# servo_air.net
KiCad netlist of a schematic drawn in EAGLE
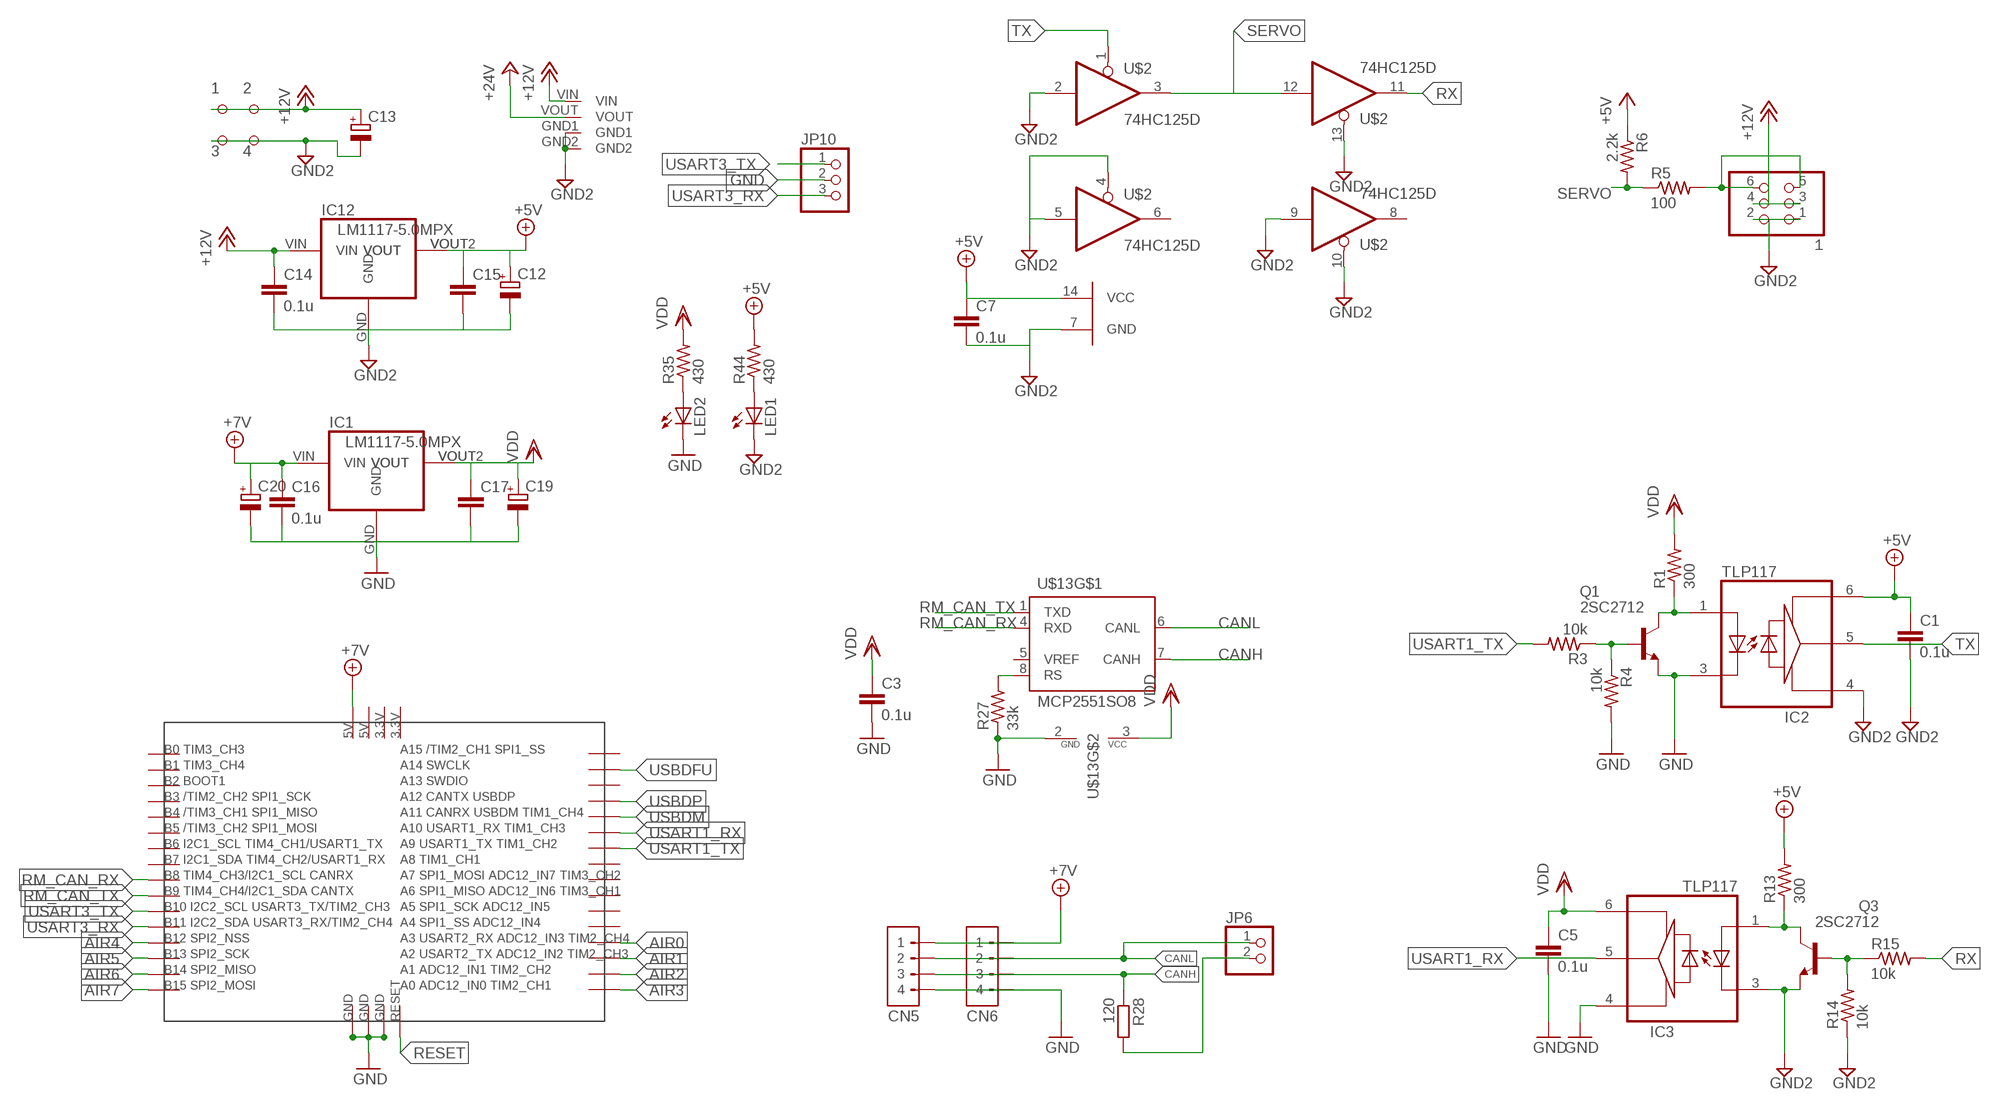
[diagram p0: schematic, sheet 1, part 1 of 2]
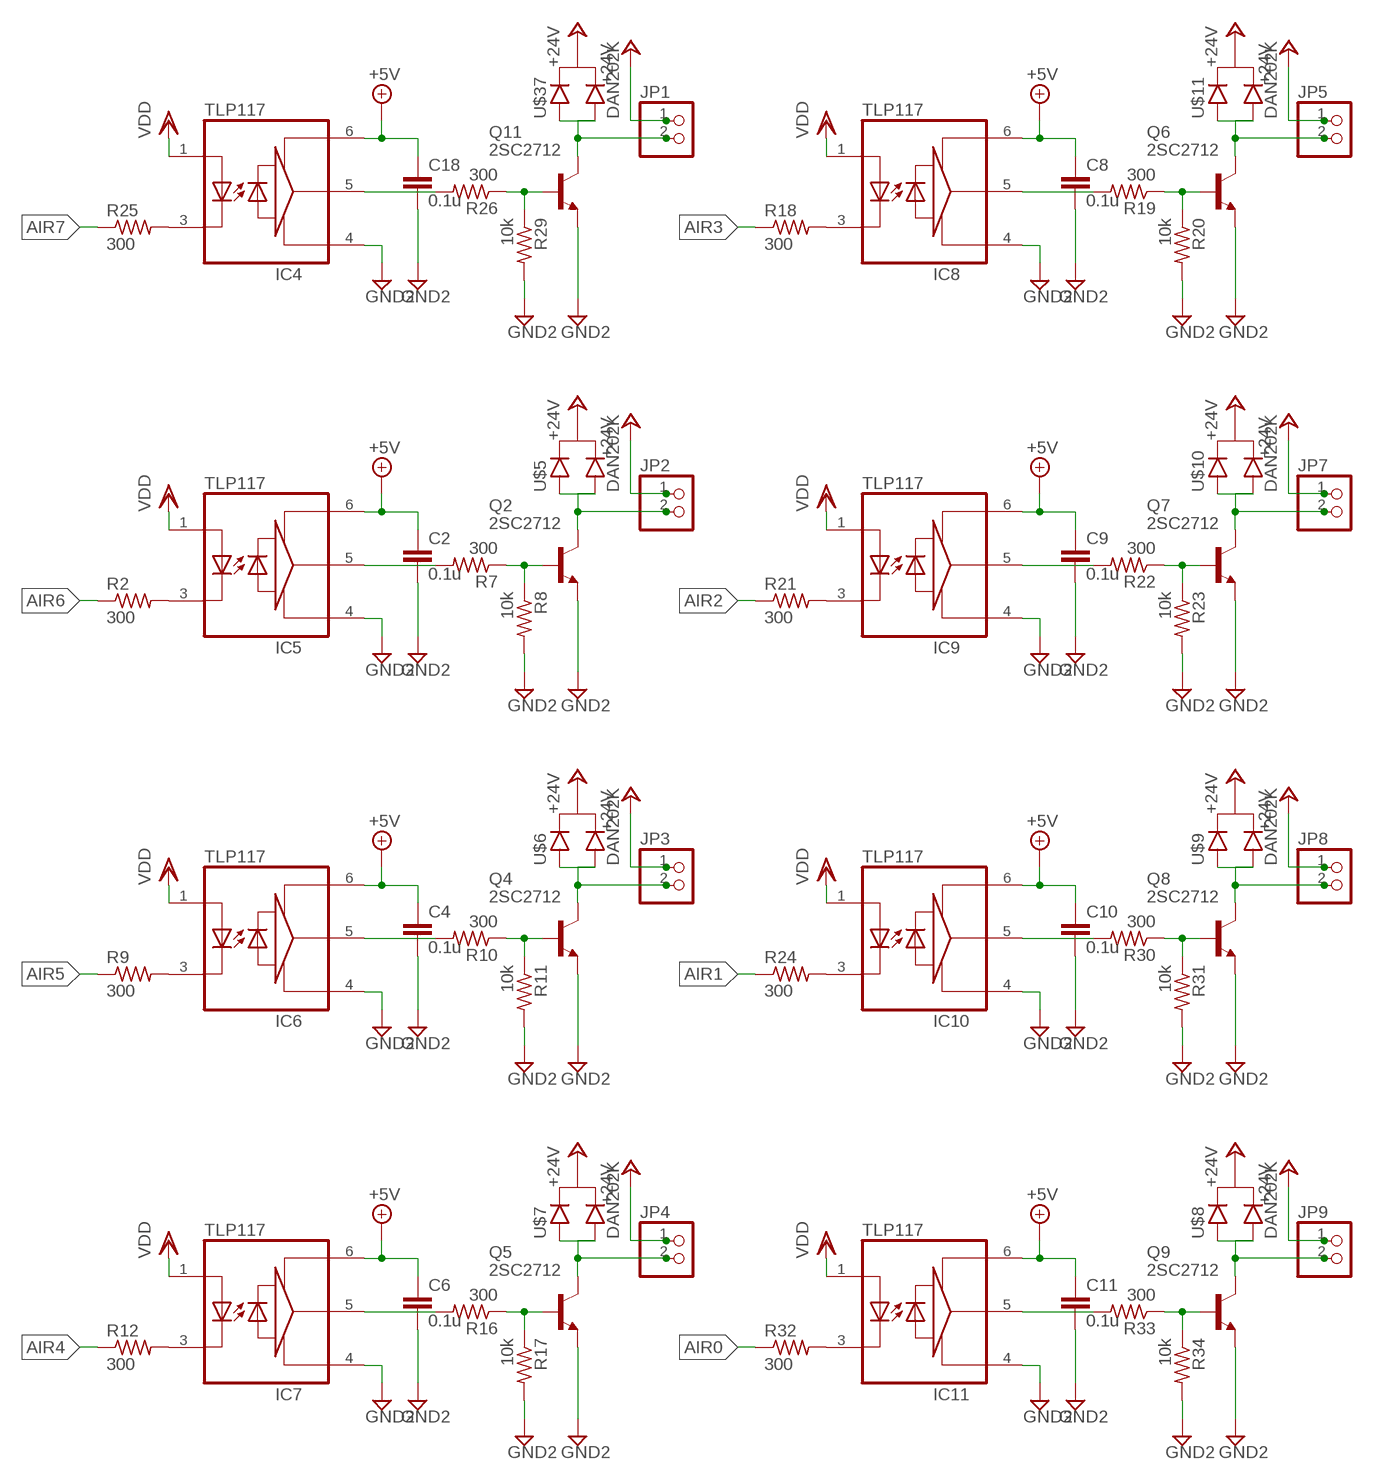
[diagram p1: schematic, sheet 1, part 2 of 2]

(export (version "E")
  (design (tool "Eeschema 10.0.6"))
  (components
    (comp (ref "C1")
      (value "0.1u")
      (footprint "eagle-import:C0603")
      (libsource (lib "eagle-import") (part "C-EUC0603"))
    )
    (comp (ref "C2")
      (value "0.1u")
      (footprint "eagle-import:C2012")
      (libsource (lib "eagle-import") (part "C-EUC2012"))
    )
    (comp (ref "C3")
      (value "0.1u")
      (footprint "eagle-import:C0603")
      (libsource (lib "eagle-import") (part "C-EUC0603"))
    )
    (comp (ref "C4")
      (value "0.1u")
      (footprint "eagle-import:C2012")
      (libsource (lib "eagle-import") (part "C-EUC2012"))
    )
    (comp (ref "C5")
      (value "0.1u")
      (footprint "eagle-import:C0603")
      (libsource (lib "eagle-import") (part "C-EUC0603"))
    )
    (comp (ref "C6")
      (value "0.1u")
      (footprint "eagle-import:C2012")
      (libsource (lib "eagle-import") (part "C-EUC2012"))
    )
    (comp (ref "C7")
      (value "0.1u")
      (footprint "eagle-import:C0603")
      (libsource (lib "eagle-import") (part "C-EUC0603"))
    )
    (comp (ref "C8")
      (value "0.1u")
      (footprint "eagle-import:C2012")
      (libsource (lib "eagle-import") (part "C-EUC2012"))
    )
    (comp (ref "C9")
      (value "0.1u")
      (footprint "eagle-import:C2012")
      (libsource (lib "eagle-import") (part "C-EUC2012"))
    )
    (comp (ref "C10")
      (value "0.1u")
      (footprint "eagle-import:C2012")
      (libsource (lib "eagle-import") (part "C-EUC2012"))
    )
    (comp (ref "C11")
      (value "0.1u")
      (footprint "eagle-import:C2012")
      (libsource (lib "eagle-import") (part "C-EUC2012"))
    )
    (comp (ref "C12")
      (value "CPOL-EUE2.5-6")
      (footprint "eagle-import:E2,5-6")
      (libsource (lib "eagle-import") (part "CPOL-EUE2.5-6"))
    )
    (comp (ref "C13")
      (value "CPOL-EUE2.5-6")
      (footprint "eagle-import:E2,5-6")
      (libsource (lib "eagle-import") (part "CPOL-EUE2.5-6"))
    )
    (comp (ref "C14")
      (value "0.1u")
      (footprint "eagle-import:C0603K")
      (libsource (lib "eagle-import") (part "resistor_C-EUC0603K"))
    )
    (comp (ref "C15")
      (value "C-EUC0603K")
      (footprint "eagle-import:C0603K")
      (libsource (lib "eagle-import") (part "resistor_C-EUC0603K"))
    )
    (comp (ref "C16")
      (value "0.1u")
      (footprint "eagle-import:C0603K")
      (libsource (lib "eagle-import") (part "resistor_C-EUC0603K"))
    )
    (comp (ref "C17")
      (value "C-EUC0603K")
      (footprint "eagle-import:C0603K")
      (libsource (lib "eagle-import") (part "resistor_C-EUC0603K"))
    )
    (comp (ref "C18")
      (value "0.1u")
      (footprint "eagle-import:C2012")
      (libsource (lib "eagle-import") (part "C-EUC2012"))
    )
    (comp (ref "C19")
      (value "CPOL-EUE2.5-6")
      (footprint "eagle-import:E2,5-6")
      (libsource (lib "eagle-import") (part "CPOL-EUE2.5-6"))
    )
    (comp (ref "C20")
      (value "CPOL-EUE2.5-6")
      (footprint "eagle-import:E2,5-6")
      (libsource (lib "eagle-import") (part "CPOL-EUE2.5-6"))
    )
    (comp (ref "CN5")
      (value "CN4-JST-XH-TOP")
      (footprint "eagle-import:JST-B4B-XH-A")
      (libsource (lib "eagle-import") (part "CN4-JST-XH-TOP"))
    )
    (comp (ref "CN6")
      (value "CN4-JST-XH-TOP")
      (footprint "eagle-import:JST-B4B-XH-A")
      (libsource (lib "eagle-import") (part "CN4-JST-XH-TOP"))
    )
    (comp (ref "IC1")
      (value "LM1117-5.0MPX")
      (footprint "eagle-import:SOT223")
      (libsource (lib "eagle-import") (part "LM1117IMP-5.0"))
    )
    (comp (ref "IC2")
      (value "TLP117")
      (footprint "eagle-import:MFSOP6")
      (libsource (lib "eagle-import") (part "TLP117"))
    )
    (comp (ref "IC3")
      (value "TLP117")
      (footprint "eagle-import:MFSOP6")
      (libsource (lib "eagle-import") (part "TLP117"))
    )
    (comp (ref "IC4")
      (value "TLP117")
      (footprint "eagle-import:MFSOP6")
      (libsource (lib "eagle-import") (part "TLP117"))
    )
    (comp (ref "IC5")
      (value "TLP117")
      (footprint "eagle-import:MFSOP6")
      (libsource (lib "eagle-import") (part "TLP117"))
    )
    (comp (ref "IC6")
      (value "TLP117")
      (footprint "eagle-import:MFSOP6")
      (libsource (lib "eagle-import") (part "TLP117"))
    )
    (comp (ref "IC7")
      (value "TLP117")
      (footprint "eagle-import:MFSOP6")
      (libsource (lib "eagle-import") (part "TLP117"))
    )
    (comp (ref "IC8")
      (value "TLP117")
      (footprint "eagle-import:MFSOP6")
      (libsource (lib "eagle-import") (part "TLP117"))
    )
    (comp (ref "IC9")
      (value "TLP117")
      (footprint "eagle-import:MFSOP6")
      (libsource (lib "eagle-import") (part "TLP117"))
    )
    (comp (ref "IC10")
      (value "TLP117")
      (footprint "eagle-import:MFSOP6")
      (libsource (lib "eagle-import") (part "TLP117"))
    )
    (comp (ref "IC11")
      (value "TLP117")
      (footprint "eagle-import:MFSOP6")
      (libsource (lib "eagle-import") (part "TLP117"))
    )
    (comp (ref "IC12")
      (value "LM1117-5.0MPX")
      (footprint "eagle-import:SOT223")
      (libsource (lib "eagle-import") (part "LM1117IMP-5.0"))
    )
    (comp (ref "JP1")
      (value "PINHD-1X2/90")
      (footprint "eagle-import:1X02_90")
      (libsource (lib "eagle-import") (part "PINHD-1X2/90"))
    )
    (comp (ref "JP2")
      (value "PINHD-1X2/90")
      (footprint "eagle-import:1X02_90")
      (libsource (lib "eagle-import") (part "PINHD-1X2/90"))
    )
    (comp (ref "JP3")
      (value "PINHD-1X2/90")
      (footprint "eagle-import:1X02_90")
      (libsource (lib "eagle-import") (part "PINHD-1X2/90"))
    )
    (comp (ref "JP4")
      (value "PINHD-1X2/90")
      (footprint "eagle-import:1X02_90")
      (libsource (lib "eagle-import") (part "PINHD-1X2/90"))
    )
    (comp (ref "JP5")
      (value "PINHD-1X2/90")
      (footprint "eagle-import:1X02_90")
      (libsource (lib "eagle-import") (part "PINHD-1X2/90"))
    )
    (comp (ref "JP6")
      (value "PINHD-1X2")
      (footprint "eagle-import:1X02")
      (libsource (lib "eagle-import") (part "PINHD-1X2"))
    )
    (comp (ref "JP7")
      (value "PINHD-1X2/90")
      (footprint "eagle-import:1X02_90")
      (libsource (lib "eagle-import") (part "PINHD-1X2/90"))
    )
    (comp (ref "JP8")
      (value "PINHD-1X2/90")
      (footprint "eagle-import:1X02_90")
      (libsource (lib "eagle-import") (part "PINHD-1X2/90"))
    )
    (comp (ref "JP9")
      (value "PINHD-1X2/90")
      (footprint "eagle-import:1X02_90")
      (libsource (lib "eagle-import") (part "PINHD-1X2/90"))
    )
    (comp (ref "JP10")
      (value "PINHD-1X3")
      (footprint "eagle-import:1X03")
      (libsource (lib "eagle-import") (part "PINHD-1X3"))
    )
    (comp (ref "LED1")
      (value "LEDCHIPLED_1206")
      (footprint "eagle-import:CHIPLED_1206")
      (libsource (lib "eagle-import") (part "LEDCHIPLED_1206"))
    )
    (comp (ref "LED2")
      (value "LEDCHIPLED_1206")
      (footprint "eagle-import:CHIPLED_1206")
      (libsource (lib "eagle-import") (part "LEDCHIPLED_1206"))
    )
    (comp (ref "Q1")
      (value "2SC2712")
      (footprint "eagle-import:SC-59(TYPE1)")
      (libsource (lib "eagle-import") (part "2SC2712"))
    )
    (comp (ref "Q2")
      (value "2SC2712")
      (footprint "eagle-import:SC-59(TYPE1)")
      (libsource (lib "eagle-import") (part "2SC2712"))
    )
    (comp (ref "Q3")
      (value "2SC2712")
      (footprint "eagle-import:SC-59(TYPE1)")
      (libsource (lib "eagle-import") (part "2SC2712"))
    )
    (comp (ref "Q4")
      (value "2SC2712")
      (footprint "eagle-import:SC-59(TYPE1)")
      (libsource (lib "eagle-import") (part "2SC2712"))
    )
    (comp (ref "Q5")
      (value "2SC2712")
      (footprint "eagle-import:SC-59(TYPE1)")
      (libsource (lib "eagle-import") (part "2SC2712"))
    )
    (comp (ref "Q6")
      (value "2SC2712")
      (footprint "eagle-import:SC-59(TYPE1)")
      (libsource (lib "eagle-import") (part "2SC2712"))
    )
    (comp (ref "Q7")
      (value "2SC2712")
      (footprint "eagle-import:SC-59(TYPE1)")
      (libsource (lib "eagle-import") (part "2SC2712"))
    )
    (comp (ref "Q8")
      (value "2SC2712")
      (footprint "eagle-import:SC-59(TYPE1)")
      (libsource (lib "eagle-import") (part "2SC2712"))
    )
    (comp (ref "Q9")
      (value "2SC2712")
      (footprint "eagle-import:SC-59(TYPE1)")
      (libsource (lib "eagle-import") (part "2SC2712"))
    )
    (comp (ref "Q11")
      (value "2SC2712")
      (footprint "eagle-import:SC-59(TYPE1)")
      (libsource (lib "eagle-import") (part "2SC2712"))
    )
    (comp (ref "R1")
      (value "300")
      (footprint "eagle-import:R0603")
      (libsource (lib "eagle-import") (part "R-US_R0603"))
    )
    (comp (ref "R2")
      (value "300")
      (footprint "eagle-import:R2012")
      (libsource (lib "eagle-import") (part "R-US_R2012"))
    )
    (comp (ref "R3")
      (value "10k")
      (footprint "eagle-import:R0603")
      (libsource (lib "eagle-import") (part "R-US_R0603"))
    )
    (comp (ref "R4")
      (value "10k")
      (footprint "eagle-import:R0603")
      (libsource (lib "eagle-import") (part "R-US_R0603"))
    )
    (comp (ref "R5")
      (value "100")
      (footprint "eagle-import:R0603")
      (libsource (lib "eagle-import") (part "R-US_R0603"))
    )
    (comp (ref "R6")
      (value "2.2k")
      (footprint "eagle-import:R0603")
      (libsource (lib "eagle-import") (part "R-US_R0603"))
    )
    (comp (ref "R7")
      (value "300")
      (footprint "eagle-import:R2012")
      (libsource (lib "eagle-import") (part "R-US_R2012"))
    )
    (comp (ref "R8")
      (value "10k")
      (footprint "eagle-import:R2012")
      (libsource (lib "eagle-import") (part "R-US_R2012"))
    )
    (comp (ref "R9")
      (value "300")
      (footprint "eagle-import:R2012")
      (libsource (lib "eagle-import") (part "R-US_R2012"))
    )
    (comp (ref "R10")
      (value "300")
      (footprint "eagle-import:R2012")
      (libsource (lib "eagle-import") (part "R-US_R2012"))
    )
    (comp (ref "R11")
      (value "10k")
      (footprint "eagle-import:R2012")
      (libsource (lib "eagle-import") (part "R-US_R2012"))
    )
    (comp (ref "R12")
      (value "300")
      (footprint "eagle-import:R2012")
      (libsource (lib "eagle-import") (part "R-US_R2012"))
    )
    (comp (ref "R13")
      (value "300")
      (footprint "eagle-import:R0603")
      (libsource (lib "eagle-import") (part "R-US_R0603"))
    )
    (comp (ref "R14")
      (value "10k")
      (footprint "eagle-import:R0603")
      (libsource (lib "eagle-import") (part "R-US_R0603"))
    )
    (comp (ref "R15")
      (value "10k")
      (footprint "eagle-import:R0603")
      (libsource (lib "eagle-import") (part "R-US_R0603"))
    )
    (comp (ref "R16")
      (value "300")
      (footprint "eagle-import:R2012")
      (libsource (lib "eagle-import") (part "R-US_R2012"))
    )
    (comp (ref "R17")
      (value "10k")
      (footprint "eagle-import:R2012")
      (libsource (lib "eagle-import") (part "R-US_R2012"))
    )
    (comp (ref "R18")
      (value "300")
      (footprint "eagle-import:R2012")
      (libsource (lib "eagle-import") (part "R-US_R2012"))
    )
    (comp (ref "R19")
      (value "300")
      (footprint "eagle-import:R2012")
      (libsource (lib "eagle-import") (part "R-US_R2012"))
    )
    (comp (ref "R20")
      (value "10k")
      (footprint "eagle-import:R2012")
      (libsource (lib "eagle-import") (part "R-US_R2012"))
    )
    (comp (ref "R21")
      (value "300")
      (footprint "eagle-import:R2012")
      (libsource (lib "eagle-import") (part "R-US_R2012"))
    )
    (comp (ref "R22")
      (value "300")
      (footprint "eagle-import:R2012")
      (libsource (lib "eagle-import") (part "R-US_R2012"))
    )
    (comp (ref "R23")
      (value "10k")
      (footprint "eagle-import:R2012")
      (libsource (lib "eagle-import") (part "R-US_R2012"))
    )
    (comp (ref "R24")
      (value "300")
      (footprint "eagle-import:R2012")
      (libsource (lib "eagle-import") (part "R-US_R2012"))
    )
    (comp (ref "R25")
      (value "300")
      (footprint "eagle-import:R2012")
      (libsource (lib "eagle-import") (part "R-US_R2012"))
    )
    (comp (ref "R26")
      (value "300")
      (footprint "eagle-import:R2012")
      (libsource (lib "eagle-import") (part "R-US_R2012"))
    )
    (comp (ref "R27")
      (value "33k")
      (footprint "eagle-import:R0603")
      (libsource (lib "eagle-import") (part "resistor_R-US_R0603"))
    )
    (comp (ref "R28")
      (value "120")
      (footprint "eagle-import:R0603")
      (libsource (lib "eagle-import") (part "R-EU_R0603"))
    )
    (comp (ref "R29")
      (value "10k")
      (footprint "eagle-import:R2012")
      (libsource (lib "eagle-import") (part "R-US_R2012"))
    )
    (comp (ref "R30")
      (value "300")
      (footprint "eagle-import:R2012")
      (libsource (lib "eagle-import") (part "R-US_R2012"))
    )
    (comp (ref "R31")
      (value "10k")
      (footprint "eagle-import:R2012")
      (libsource (lib "eagle-import") (part "R-US_R2012"))
    )
    (comp (ref "R32")
      (value "300")
      (footprint "eagle-import:R2012")
      (libsource (lib "eagle-import") (part "R-US_R2012"))
    )
    (comp (ref "R33")
      (value "300")
      (footprint "eagle-import:R2012")
      (libsource (lib "eagle-import") (part "R-US_R2012"))
    )
    (comp (ref "R34")
      (value "10k")
      (footprint "eagle-import:R2012")
      (libsource (lib "eagle-import") (part "R-US_R2012"))
    )
    (comp (ref "R35")
      (value "430")
      (footprint "eagle-import:M2012")
      (libsource (lib "eagle-import") (part "R-US_M2012"))
    )
    (comp (ref "R44")
      (value "430")
      (footprint "eagle-import:M2012")
      (libsource (lib "eagle-import") (part "R-US_M2012"))
    )
    (comp (ref "U$1")
      (value "STBE_MINI")
      (footprint "eagle-import:STBEE_MINI")
      (libsource (lib "eagle-import") (part "STBE_MINI"))
    )
    (comp (ref "U$2")
      (value "74HC125D")
      (footprint "eagle-import:SO14")
      (libsource (lib "eagle-import") (part "74HC125D"))
    )
    (comp (ref "U$3")
      (value "5569")
      (footprint "eagle-import:5569")
      (libsource (lib "eagle-import") (part "5569"))
    )
    (comp (ref "U$4")
      (value "LT3580")
      (footprint "eagle-import:LT3580")
      (libsource (lib "eagle-import") (part "LT3580"))
    )
    (comp (ref "U$5")
      (value "DAN202K")
      (footprint "eagle-import:SC-59")
      (libsource (lib "eagle-import") (part "DAN202K"))
    )
    (comp (ref "U$6")
      (value "DAN202K")
      (footprint "eagle-import:SC-59")
      (libsource (lib "eagle-import") (part "DAN202K"))
    )
    (comp (ref "U$7")
      (value "DAN202K")
      (footprint "eagle-import:SC-59")
      (libsource (lib "eagle-import") (part "DAN202K"))
    )
    (comp (ref "U$8")
      (value "DAN202K")
      (footprint "eagle-import:SC-59")
      (libsource (lib "eagle-import") (part "DAN202K"))
    )
    (comp (ref "U$9")
      (value "DAN202K")
      (footprint "eagle-import:SC-59")
      (libsource (lib "eagle-import") (part "DAN202K"))
    )
    (comp (ref "U$10")
      (value "DAN202K")
      (footprint "eagle-import:SC-59")
      (libsource (lib "eagle-import") (part "DAN202K"))
    )
    (comp (ref "U$11")
      (value "DAN202K")
      (footprint "eagle-import:SC-59")
      (libsource (lib "eagle-import") (part "DAN202K"))
    )
    (comp (ref "U$13")
      (value "MCP2551SO8")
      (footprint "eagle-import:SO08")
      (libsource (lib "eagle-import") (part "MCP2551SO8"))
    )
    (comp (ref "U$37")
      (value "DAN202K")
      (footprint "eagle-import:SC-59")
      (libsource (lib "eagle-import") (part "DAN202K"))
    )
    (comp (ref "　　1")
      (value "PINHD-2X3/90")
      (footprint "eagle-import:2X03_90")
      (libsource (lib "eagle-import") (part "PINHD-2X3/90"))
    )
  )
  (nets
    (net (code "1") (name "+5V") (class "Default")
      (node (ref "C1") (pin "1") (pinfunction "1_1") (pintype "passive"))
      (node (ref "C10") (pin "1") (pinfunction "1_1") (pintype "passive"))
      (node (ref "C11") (pin "1") (pinfunction "1_1") (pintype "passive"))
      (node (ref "C12") (pin "+") (pinfunction "+_+") (pintype "passive"))
      (node (ref "C15") (pin "1") (pinfunction "1_1") (pintype "passive"))
      (node (ref "C18") (pin "1") (pinfunction "1_1") (pintype "passive"))
      (node (ref "C2") (pin "1") (pinfunction "1_1") (pintype "passive"))
      (node (ref "C4") (pin "1") (pinfunction "1_1") (pintype "passive"))
      (node (ref "C6") (pin "1") (pinfunction "1_1") (pintype "passive"))
      (node (ref "C7") (pin "1") (pinfunction "1_1") (pintype "passive"))
      (node (ref "C8") (pin "1") (pinfunction "1_1") (pintype "passive"))
      (node (ref "C9") (pin "1") (pinfunction "1_1") (pintype "passive"))
      (node (ref "IC10") (pin "6") (pinfunction "VCC_6") (pintype "power_in"))
      (node (ref "IC11") (pin "6") (pinfunction "VCC_6") (pintype "power_in"))
      (node (ref "IC12") (pin "VOUT") (pinfunction "VOUT_VOUT") (pintype "output"))
      (node (ref "IC12") (pin "VOUT2") (pinfunction "VOUT_VOUT2") (pintype "output"))
      (node (ref "IC2") (pin "6") (pinfunction "VCC_6") (pintype "power_in"))
      (node (ref "IC4") (pin "6") (pinfunction "VCC_6") (pintype "power_in"))
      (node (ref "IC5") (pin "6") (pinfunction "VCC_6") (pintype "power_in"))
      (node (ref "IC6") (pin "6") (pinfunction "VCC_6") (pintype "power_in"))
      (node (ref "IC7") (pin "6") (pinfunction "VCC_6") (pintype "power_in"))
      (node (ref "IC8") (pin "6") (pinfunction "VCC_6") (pintype "power_in"))
      (node (ref "IC9") (pin "6") (pinfunction "VCC_6") (pintype "power_in"))
      (node (ref "R13") (pin "2") (pinfunction "2_2") (pintype "passive"))
      (node (ref "R44") (pin "2") (pinfunction "2_2") (pintype "passive"))
      (node (ref "R6") (pin "1") (pinfunction "1_1") (pintype "passive"))
      (node (ref "U$2") (pin "14") (pinfunction "VCC_14") (pintype "bidirectional"))
    )
    (net (code "2") (name "+7V") (class "Default")
      (node (ref "C16") (pin "1") (pinfunction "1_1") (pintype "passive"))
      (node (ref "C20") (pin "+") (pinfunction "+_+") (pintype "passive"))
      (node (ref "CN5") (pin "1") (pinfunction "1_1") (pintype "passive"))
      (node (ref "CN6") (pin "1") (pinfunction "1_1") (pintype "passive"))
      (node (ref "IC1") (pin "VIN") (pinfunction "VIN_VIN") (pintype "input"))
      (node (ref "U$1") (pin "5V1") (pinfunction "5V1_5V1") (pintype "bidirectional"))
    )
    (net (code "3") (name "+12V") (class "Default")
      (node (ref "C13") (pin "+") (pinfunction "+_+") (pintype "passive"))
      (node (ref "C14") (pin "1") (pinfunction "1_1") (pintype "passive"))
      (node (ref "IC12") (pin "VIN") (pinfunction "VIN_VIN") (pintype "input"))
      (node (ref "U$3") (pin "1") (pinfunction "1_1") (pintype "bidirectional"))
      (node (ref "U$3") (pin "2") (pinfunction "2_2") (pintype "bidirectional"))
      (node (ref "U$4") (pin "VIN") (pinfunction "VIN_VIN") (pintype "bidirectional"))
      (node (ref "　　1") (pin "3") (pinfunction "3_3") (pintype "passive"))
      (node (ref "　　1") (pin "4") (pinfunction "4_4") (pintype "passive"))
    )
    (net (code "4") (name "+24V") (class "Default")
      (node (ref "JP1") (pin "1") (pinfunction "1_1") (pintype "passive"))
      (node (ref "JP2") (pin "1") (pinfunction "1_1") (pintype "passive"))
      (node (ref "JP3") (pin "1") (pinfunction "1_1") (pintype "passive"))
      (node (ref "JP4") (pin "1") (pinfunction "1_1") (pintype "passive"))
      (node (ref "JP5") (pin "1") (pinfunction "1_1") (pintype "passive"))
      (node (ref "JP7") (pin "1") (pinfunction "1_1") (pintype "passive"))
      (node (ref "JP8") (pin "1") (pinfunction "1_1") (pintype "passive"))
      (node (ref "JP9") (pin "1") (pinfunction "1_1") (pintype "passive"))
      (node (ref "U$10") (pin "K") (pinfunction "K_K") (pintype "passive"))
      (node (ref "U$11") (pin "K") (pinfunction "K_K") (pintype "passive"))
      (node (ref "U$37") (pin "K") (pinfunction "K_K") (pintype "passive"))
      (node (ref "U$4") (pin "VOUT") (pinfunction "VOUT_VOUT") (pintype "bidirectional"))
      (node (ref "U$5") (pin "K") (pinfunction "K_K") (pintype "passive"))
      (node (ref "U$6") (pin "K") (pinfunction "K_K") (pintype "passive"))
      (node (ref "U$7") (pin "K") (pinfunction "K_K") (pintype "passive"))
      (node (ref "U$8") (pin "K") (pinfunction "K_K") (pintype "passive"))
      (node (ref "U$9") (pin "K") (pinfunction "K_K") (pintype "passive"))
    )
    (net (code "5") (name "AIR0") (class "Default")
      (node (ref "R32") (pin "1") (pinfunction "1_1") (pintype "passive"))
      (node (ref "U$1") (pin "A3") (pinfunction "A3_A3") (pintype "bidirectional"))
    )
    (net (code "6") (name "AIR1") (class "Default")
      (node (ref "R24") (pin "1") (pinfunction "1_1") (pintype "passive"))
      (node (ref "U$1") (pin "A2") (pinfunction "A2_A2") (pintype "bidirectional"))
    )
    (net (code "7") (name "AIR2") (class "Default")
      (node (ref "R21") (pin "1") (pinfunction "1_1") (pintype "passive"))
      (node (ref "U$1") (pin "A1") (pinfunction "A1_A1") (pintype "bidirectional"))
    )
    (net (code "8") (name "AIR3") (class "Default")
      (node (ref "R18") (pin "1") (pinfunction "1_1") (pintype "passive"))
      (node (ref "U$1") (pin "A0") (pinfunction "A0_A0") (pintype "bidirectional"))
    )
    (net (code "9") (name "AIR4") (class "Default")
      (node (ref "R12") (pin "1") (pinfunction "1_1") (pintype "passive"))
      (node (ref "U$1") (pin "B12") (pinfunction "B12_B12") (pintype "bidirectional"))
    )
    (net (code "10") (name "AIR5") (class "Default")
      (node (ref "R9") (pin "1") (pinfunction "1_1") (pintype "passive"))
      (node (ref "U$1") (pin "B13") (pinfunction "B13_B13") (pintype "bidirectional"))
    )
    (net (code "11") (name "AIR6") (class "Default")
      (node (ref "R2") (pin "1") (pinfunction "1_1") (pintype "passive"))
      (node (ref "U$1") (pin "B14") (pinfunction "B14_B14") (pintype "bidirectional"))
    )
    (net (code "12") (name "AIR7") (class "Default")
      (node (ref "R25") (pin "1") (pinfunction "1_1") (pintype "passive"))
      (node (ref "U$1") (pin "B15") (pinfunction "B15_B15") (pintype "bidirectional"))
    )
    (net (code "13") (name "CANH") (class "Default")
      (node (ref "CN5") (pin "3") (pinfunction "3_3") (pintype "passive"))
      (node (ref "CN6") (pin "3") (pinfunction "3_3") (pintype "passive"))
      (node (ref "R28") (pin "1") (pinfunction "1_1") (pintype "passive"))
      (node (ref "U$13") (pin "7") (pinfunction "CANH_7") (pintype "bidirectional"))
    )
    (net (code "14") (name "CANL") (class "Default")
      (node (ref "CN5") (pin "2") (pinfunction "2_2") (pintype "passive"))
      (node (ref "CN6") (pin "2") (pinfunction "2_2") (pintype "passive"))
      (node (ref "JP6") (pin "1") (pinfunction "1_1") (pintype "passive"))
      (node (ref "U$13") (pin "6") (pinfunction "CANL_6") (pintype "bidirectional"))
    )
    (net (code "15") (name "GND") (class "Default")
      (node (ref "C16") (pin "2") (pinfunction "2_2") (pintype "passive"))
      (node (ref "C17") (pin "2") (pinfunction "2_2") (pintype "passive"))
      (node (ref "C19") (pin "-") (pinfunction "-_-") (pintype "passive"))
      (node (ref "C20") (pin "-") (pinfunction "-_-") (pintype "passive"))
      (node (ref "C3") (pin "2") (pinfunction "2_2") (pintype "passive"))
      (node (ref "C5") (pin "2") (pinfunction "2_2") (pintype "passive"))
      (node (ref "CN5") (pin "4") (pinfunction "4_4") (pintype "passive"))
      (node (ref "CN6") (pin "4") (pinfunction "4_4") (pintype "passive"))
      (node (ref "IC1") (pin "GND") (pinfunction "GND_GND") (pintype "power_in"))
      (node (ref "IC2") (pin "3") (pinfunction "3_3") (pintype "output"))
      (node (ref "IC3") (pin "4") (pinfunction "GND_4") (pintype "power_in"))
      (node (ref "JP10") (pin "2") (pinfunction "2_2") (pintype "passive"))
      (node (ref "LED2") (pin "C") (pinfunction "C_C") (pintype "passive"))
      (node (ref "Q1") (pin "E") (pinfunction "E_E") (pintype "passive"))
      (node (ref "R27") (pin "1") (pinfunction "1_1") (pintype "passive"))
      (node (ref "R4") (pin "2") (pinfunction "2_2") (pintype "passive"))
      (node (ref "U$1") (pin "GND1") (pinfunction "GND1_GND1") (pintype "bidirectional"))
      (node (ref "U$1") (pin "GND2") (pinfunction "GND2_GND2") (pintype "bidirectional"))
      (node (ref "U$1") (pin "GND3") (pinfunction "GND3_GND3") (pintype "bidirectional"))
      (node (ref "U$13") (pin "2") (pinfunction "GND_2") (pintype "power_in"))
    )
    (net (code "16") (name "GND2") (class "Default")
      (node (ref "C1") (pin "2") (pinfunction "2_2") (pintype "passive"))
      (node (ref "C10") (pin "2") (pinfunction "2_2") (pintype "passive"))
      (node (ref "C11") (pin "2") (pinfunction "2_2") (pintype "passive"))
      (node (ref "C12") (pin "-") (pinfunction "-_-") (pintype "passive"))
      (node (ref "C13") (pin "-") (pinfunction "-_-") (pintype "passive"))
      (node (ref "C14") (pin "2") (pinfunction "2_2") (pintype "passive"))
      (node (ref "C15") (pin "2") (pinfunction "2_2") (pintype "passive"))
      (node (ref "C18") (pin "2") (pinfunction "2_2") (pintype "passive"))
      (node (ref "C2") (pin "2") (pinfunction "2_2") (pintype "passive"))
      (node (ref "C4") (pin "2") (pinfunction "2_2") (pintype "passive"))
      (node (ref "C6") (pin "2") (pinfunction "2_2") (pintype "passive"))
      (node (ref "C7") (pin "2") (pinfunction "2_2") (pintype "passive"))
      (node (ref "C8") (pin "2") (pinfunction "2_2") (pintype "passive"))
      (node (ref "C9") (pin "2") (pinfunction "2_2") (pintype "passive"))
      (node (ref "IC10") (pin "4") (pinfunction "GND_4") (pintype "power_in"))
      (node (ref "IC11") (pin "4") (pinfunction "GND_4") (pintype "power_in"))
      (node (ref "IC12") (pin "GND") (pinfunction "GND_GND") (pintype "power_in"))
      (node (ref "IC2") (pin "4") (pinfunction "GND_4") (pintype "power_in"))
      (node (ref "IC3") (pin "3") (pinfunction "3_3") (pintype "output"))
      (node (ref "IC4") (pin "4") (pinfunction "GND_4") (pintype "power_in"))
      (node (ref "IC5") (pin "4") (pinfunction "GND_4") (pintype "power_in"))
      (node (ref "IC6") (pin "4") (pinfunction "GND_4") (pintype "power_in"))
      (node (ref "IC7") (pin "4") (pinfunction "GND_4") (pintype "power_in"))
      (node (ref "IC8") (pin "4") (pinfunction "GND_4") (pintype "power_in"))
      (node (ref "IC9") (pin "4") (pinfunction "GND_4") (pintype "power_in"))
      (node (ref "LED1") (pin "C") (pinfunction "C_C") (pintype "passive"))
      (node (ref "Q11") (pin "E") (pinfunction "E_E") (pintype "passive"))
      (node (ref "Q2") (pin "E") (pinfunction "E_E") (pintype "passive"))
      (node (ref "Q3") (pin "E") (pinfunction "E_E") (pintype "passive"))
      (node (ref "Q4") (pin "E") (pinfunction "E_E") (pintype "passive"))
      (node (ref "Q5") (pin "E") (pinfunction "E_E") (pintype "passive"))
      (node (ref "Q6") (pin "E") (pinfunction "E_E") (pintype "passive"))
      (node (ref "Q7") (pin "E") (pinfunction "E_E") (pintype "passive"))
      (node (ref "Q8") (pin "E") (pinfunction "E_E") (pintype "passive"))
      (node (ref "Q9") (pin "E") (pinfunction "E_E") (pintype "passive"))
      (node (ref "R11") (pin "2") (pinfunction "2_2") (pintype "passive"))
      (node (ref "R14") (pin "1") (pinfunction "1_1") (pintype "passive"))
      (node (ref "R17") (pin "2") (pinfunction "2_2") (pintype "passive"))
      (node (ref "R20") (pin "2") (pinfunction "2_2") (pintype "passive"))
      (node (ref "R23") (pin "2") (pinfunction "2_2") (pintype "passive"))
      (node (ref "R29") (pin "2") (pinfunction "2_2") (pintype "passive"))
      (node (ref "R31") (pin "2") (pinfunction "2_2") (pintype "passive"))
      (node (ref "R34") (pin "2") (pinfunction "2_2") (pintype "passive"))
      (node (ref "R8") (pin "2") (pinfunction "2_2") (pintype "passive"))
      (node (ref "U$2") (pin "10") (pinfunction "3OE_10") (pintype "input"))
      (node (ref "U$2") (pin "13") (pinfunction "4OE_13") (pintype "input"))
      (node (ref "U$2") (pin "2") (pinfunction "1A_2") (pintype "input"))
      (node (ref "U$2") (pin "4") (pinfunction "2OE_4") (pintype "input"))
      (node (ref "U$2") (pin "5") (pinfunction "2A_5") (pintype "input"))
      (node (ref "U$2") (pin "7") (pinfunction "GND_7") (pintype "bidirectional"))
      (node (ref "U$2") (pin "9") (pinfunction "3A_9") (pintype "input"))
      (node (ref "U$3") (pin "3") (pinfunction "3_3") (pintype "bidirectional"))
      (node (ref "U$3") (pin "4") (pinfunction "4_4") (pintype "bidirectional"))
      (node (ref "U$4") (pin "GND1") (pinfunction "GND1_GND1") (pintype "bidirectional"))
      (node (ref "U$4") (pin "GND2") (pinfunction "GND2_GND2") (pintype "bidirectional"))
      (node (ref "　　1") (pin "1") (pinfunction "1_1") (pintype "passive"))
      (node (ref "　　1") (pin "2") (pinfunction "2_2") (pintype "passive"))
    )
    (net (code "17") (name "Net-(IC2-Pad1)") (class "Default")
      (node (ref "IC2") (pin "1") (pinfunction "1_1") (pintype "input"))
      (node (ref "Q1") (pin "C") (pinfunction "C_C") (pintype "passive"))
      (node (ref "R1") (pin "1") (pinfunction "1_1") (pintype "passive"))
    )
    (net (code "18") (name "Net-(IC3-Pad1)") (class "Default")
      (node (ref "IC3") (pin "1") (pinfunction "1_1") (pintype "input"))
      (node (ref "Q3") (pin "C") (pinfunction "C_C") (pintype "passive"))
      (node (ref "R13") (pin "1") (pinfunction "1_1") (pintype "passive"))
    )
    (net (code "19") (name "Net-(IC4-Pad3)") (class "Default")
      (node (ref "IC4") (pin "3") (pinfunction "3_3") (pintype "output"))
      (node (ref "R25") (pin "2") (pinfunction "2_2") (pintype "passive"))
    )
    (net (code "20") (name "Net-(IC4-Pad5)") (class "Default")
      (node (ref "IC4") (pin "5") (pinfunction "5_5") (pintype "output"))
      (node (ref "R26") (pin "2") (pinfunction "2_2") (pintype "passive"))
    )
    (net (code "21") (name "Net-(IC5-Pad3)") (class "Default")
      (node (ref "IC5") (pin "3") (pinfunction "3_3") (pintype "output"))
      (node (ref "R2") (pin "2") (pinfunction "2_2") (pintype "passive"))
    )
    (net (code "22") (name "Net-(IC5-Pad5)") (class "Default")
      (node (ref "IC5") (pin "5") (pinfunction "5_5") (pintype "output"))
      (node (ref "R7") (pin "2") (pinfunction "2_2") (pintype "passive"))
    )
    (net (code "23") (name "Net-(IC6-Pad3)") (class "Default")
      (node (ref "IC6") (pin "3") (pinfunction "3_3") (pintype "output"))
      (node (ref "R9") (pin "2") (pinfunction "2_2") (pintype "passive"))
    )
    (net (code "24") (name "Net-(IC6-Pad5)") (class "Default")
      (node (ref "IC6") (pin "5") (pinfunction "5_5") (pintype "output"))
      (node (ref "R10") (pin "2") (pinfunction "2_2") (pintype "passive"))
    )
    (net (code "25") (name "Net-(IC7-Pad3)") (class "Default")
      (node (ref "IC7") (pin "3") (pinfunction "3_3") (pintype "output"))
      (node (ref "R12") (pin "2") (pinfunction "2_2") (pintype "passive"))
    )
    (net (code "26") (name "Net-(IC7-Pad5)") (class "Default")
      (node (ref "IC7") (pin "5") (pinfunction "5_5") (pintype "output"))
      (node (ref "R16") (pin "2") (pinfunction "2_2") (pintype "passive"))
    )
    (net (code "27") (name "Net-(IC8-Pad3)") (class "Default")
      (node (ref "IC8") (pin "3") (pinfunction "3_3") (pintype "output"))
      (node (ref "R18") (pin "2") (pinfunction "2_2") (pintype "passive"))
    )
    (net (code "28") (name "Net-(IC8-Pad5)") (class "Default")
      (node (ref "IC8") (pin "5") (pinfunction "5_5") (pintype "output"))
      (node (ref "R19") (pin "2") (pinfunction "2_2") (pintype "passive"))
    )
    (net (code "29") (name "Net-(IC9-Pad3)") (class "Default")
      (node (ref "IC9") (pin "3") (pinfunction "3_3") (pintype "output"))
      (node (ref "R21") (pin "2") (pinfunction "2_2") (pintype "passive"))
    )
    (net (code "30") (name "Net-(IC9-Pad5)") (class "Default")
      (node (ref "IC9") (pin "5") (pinfunction "5_5") (pintype "output"))
      (node (ref "R22") (pin "2") (pinfunction "2_2") (pintype "passive"))
    )
    (net (code "31") (name "Net-(IC10-Pad3)") (class "Default")
      (node (ref "IC10") (pin "3") (pinfunction "3_3") (pintype "output"))
      (node (ref "R24") (pin "2") (pinfunction "2_2") (pintype "passive"))
    )
    (net (code "32") (name "Net-(IC10-Pad5)") (class "Default")
      (node (ref "IC10") (pin "5") (pinfunction "5_5") (pintype "output"))
      (node (ref "R30") (pin "2") (pinfunction "2_2") (pintype "passive"))
    )
    (net (code "33") (name "Net-(IC11-Pad3)") (class "Default")
      (node (ref "IC11") (pin "3") (pinfunction "3_3") (pintype "output"))
      (node (ref "R32") (pin "2") (pinfunction "2_2") (pintype "passive"))
    )
    (net (code "34") (name "Net-(IC11-Pad5)") (class "Default")
      (node (ref "IC11") (pin "5") (pinfunction "5_5") (pintype "output"))
      (node (ref "R33") (pin "2") (pinfunction "2_2") (pintype "passive"))
    )
    (net (code "35") (name "Net-(JP6-Pad2)") (class "Default")
      (node (ref "JP6") (pin "2") (pinfunction "2_2") (pintype "passive"))
      (node (ref "R28") (pin "2") (pinfunction "2_2") (pintype "passive"))
    )
    (net (code "36") (name "Net-(LED1-PadA)") (class "Default")
      (node (ref "LED1") (pin "A") (pinfunction "A_A") (pintype "passive"))
      (node (ref "R44") (pin "1") (pinfunction "1_1") (pintype "passive"))
    )
    (net (code "37") (name "Net-(LED2-PadA)") (class "Default")
      (node (ref "LED2") (pin "A") (pinfunction "A_A") (pintype "passive"))
      (node (ref "R35") (pin "1") (pinfunction "1_1") (pintype "passive"))
    )
    (net (code "38") (name "Net-(Q1-PadB)") (class "Default")
      (node (ref "Q1") (pin "B") (pinfunction "B_B") (pintype "passive"))
      (node (ref "R3") (pin "1") (pinfunction "1_1") (pintype "passive"))
      (node (ref "R4") (pin "1") (pinfunction "1_1") (pintype "passive"))
    )
    (net (code "39") (name "Net-(Q2-PadB)") (class "Default")
      (node (ref "Q2") (pin "B") (pinfunction "B_B") (pintype "passive"))
      (node (ref "R7") (pin "1") (pinfunction "1_1") (pintype "passive"))
      (node (ref "R8") (pin "1") (pinfunction "1_1") (pintype "passive"))
    )
    (net (code "40") (name "Net-(Q3-PadB)") (class "Default")
      (node (ref "Q3") (pin "B") (pinfunction "B_B") (pintype "passive"))
      (node (ref "R14") (pin "2") (pinfunction "2_2") (pintype "passive"))
      (node (ref "R15") (pin "1") (pinfunction "1_1") (pintype "passive"))
    )
    (net (code "41") (name "Net-(Q4-PadB)") (class "Default")
      (node (ref "Q4") (pin "B") (pinfunction "B_B") (pintype "passive"))
      (node (ref "R10") (pin "1") (pinfunction "1_1") (pintype "passive"))
      (node (ref "R11") (pin "1") (pinfunction "1_1") (pintype "passive"))
    )
    (net (code "42") (name "Net-(Q5-PadB)") (class "Default")
      (node (ref "Q5") (pin "B") (pinfunction "B_B") (pintype "passive"))
      (node (ref "R16") (pin "1") (pinfunction "1_1") (pintype "passive"))
      (node (ref "R17") (pin "1") (pinfunction "1_1") (pintype "passive"))
    )
    (net (code "43") (name "Net-(Q6-PadB)") (class "Default")
      (node (ref "Q6") (pin "B") (pinfunction "B_B") (pintype "passive"))
      (node (ref "R19") (pin "1") (pinfunction "1_1") (pintype "passive"))
      (node (ref "R20") (pin "1") (pinfunction "1_1") (pintype "passive"))
    )
    (net (code "44") (name "Net-(Q7-PadB)") (class "Default")
      (node (ref "Q7") (pin "B") (pinfunction "B_B") (pintype "passive"))
      (node (ref "R22") (pin "1") (pinfunction "1_1") (pintype "passive"))
      (node (ref "R23") (pin "1") (pinfunction "1_1") (pintype "passive"))
    )
    (net (code "45") (name "Net-(Q8-PadB)") (class "Default")
      (node (ref "Q8") (pin "B") (pinfunction "B_B") (pintype "passive"))
      (node (ref "R30") (pin "1") (pinfunction "1_1") (pintype "passive"))
      (node (ref "R31") (pin "1") (pinfunction "1_1") (pintype "passive"))
    )
    (net (code "46") (name "Net-(Q9-PadB)") (class "Default")
      (node (ref "Q9") (pin "B") (pinfunction "B_B") (pintype "passive"))
      (node (ref "R33") (pin "1") (pinfunction "1_1") (pintype "passive"))
      (node (ref "R34") (pin "1") (pinfunction "1_1") (pintype "passive"))
    )
    (net (code "47") (name "Net-(Q11-PadB)") (class "Default")
      (node (ref "Q11") (pin "B") (pinfunction "B_B") (pintype "passive"))
      (node (ref "R26") (pin "1") (pinfunction "1_1") (pintype "passive"))
      (node (ref "R29") (pin "1") (pinfunction "1_1") (pintype "passive"))
    )
    (net (code "48") (name "Net-(R5-Pad2)") (class "Default")
      (node (ref "R5") (pin "2") (pinfunction "2_2") (pintype "passive"))
      (node (ref "　　1") (pin "5") (pinfunction "5_5") (pintype "passive"))
      (node (ref "　　1") (pin "6") (pinfunction "6_6") (pintype "passive"))
    )
    (net (code "49") (name "Net-(U$5-A1)") (class "Default")
      (node (ref "JP2") (pin "2") (pinfunction "2_2") (pintype "passive"))
      (node (ref "Q2") (pin "C") (pinfunction "C_C") (pintype "passive"))
      (node (ref "U$5") (pin "A@1") (pinfunction "A1_A@1") (pintype "passive"))
      (node (ref "U$5") (pin "A@2") (pinfunction "A2_A@2") (pintype "passive"))
    )
    (net (code "50") (name "Net-(U$6-A1)") (class "Default")
      (node (ref "JP3") (pin "2") (pinfunction "2_2") (pintype "passive"))
      (node (ref "Q4") (pin "C") (pinfunction "C_C") (pintype "passive"))
      (node (ref "U$6") (pin "A@1") (pinfunction "A1_A@1") (pintype "passive"))
      (node (ref "U$6") (pin "A@2") (pinfunction "A2_A@2") (pintype "passive"))
    )
    (net (code "51") (name "Net-(U$7-A1)") (class "Default")
      (node (ref "JP4") (pin "2") (pinfunction "2_2") (pintype "passive"))
      (node (ref "Q5") (pin "C") (pinfunction "C_C") (pintype "passive"))
      (node (ref "U$7") (pin "A@1") (pinfunction "A1_A@1") (pintype "passive"))
      (node (ref "U$7") (pin "A@2") (pinfunction "A2_A@2") (pintype "passive"))
    )
    (net (code "52") (name "Net-(U$8-A1)") (class "Default")
      (node (ref "JP9") (pin "2") (pinfunction "2_2") (pintype "passive"))
      (node (ref "Q9") (pin "C") (pinfunction "C_C") (pintype "passive"))
      (node (ref "U$8") (pin "A@1") (pinfunction "A1_A@1") (pintype "passive"))
      (node (ref "U$8") (pin "A@2") (pinfunction "A2_A@2") (pintype "passive"))
    )
    (net (code "53") (name "Net-(U$9-A1)") (class "Default")
      (node (ref "JP8") (pin "2") (pinfunction "2_2") (pintype "passive"))
      (node (ref "Q8") (pin "C") (pinfunction "C_C") (pintype "passive"))
      (node (ref "U$9") (pin "A@1") (pinfunction "A1_A@1") (pintype "passive"))
      (node (ref "U$9") (pin "A@2") (pinfunction "A2_A@2") (pintype "passive"))
    )
    (net (code "54") (name "Net-(U$10-A1)") (class "Default")
      (node (ref "JP7") (pin "2") (pinfunction "2_2") (pintype "passive"))
      (node (ref "Q7") (pin "C") (pinfunction "C_C") (pintype "passive"))
      (node (ref "U$10") (pin "A@1") (pinfunction "A1_A@1") (pintype "passive"))
      (node (ref "U$10") (pin "A@2") (pinfunction "A2_A@2") (pintype "passive"))
    )
    (net (code "55") (name "Net-(U$11-A1)") (class "Default")
      (node (ref "JP5") (pin "2") (pinfunction "2_2") (pintype "passive"))
      (node (ref "Q6") (pin "C") (pinfunction "C_C") (pintype "passive"))
      (node (ref "U$11") (pin "A@1") (pinfunction "A1_A@1") (pintype "passive"))
      (node (ref "U$11") (pin "A@2") (pinfunction "A2_A@2") (pintype "passive"))
    )
    (net (code "56") (name "Net-(U$13A-RS)") (class "Default")
      (node (ref "R27") (pin "2") (pinfunction "2_2") (pintype "passive"))
      (node (ref "U$13") (pin "8") (pinfunction "RS_8") (pintype "bidirectional"))
    )
    (net (code "57") (name "Net-(U$37-A1)") (class "Default")
      (node (ref "JP1") (pin "2") (pinfunction "2_2") (pintype "passive"))
      (node (ref "Q11") (pin "C") (pinfunction "C_C") (pintype "passive"))
      (node (ref "U$37") (pin "A@1") (pinfunction "A1_A@1") (pintype "passive"))
      (node (ref "U$37") (pin "A@2") (pinfunction "A2_A@2") (pintype "passive"))
    )
    (net (code "58") (name "RESET") (class "Default")
      (node (ref "U$1") (pin "RESET") (pinfunction "RESET_RESET") (pintype "bidirectional"))
    )
    (net (code "59") (name "RM_CAN_RX") (class "Default")
      (node (ref "U$1") (pin "B8") (pinfunction "B8_B8") (pintype "bidirectional"))
      (node (ref "U$13") (pin "4") (pinfunction "RXD_4") (pintype "bidirectional"))
    )
    (net (code "60") (name "RM_CAN_TX") (class "Default")
      (node (ref "U$1") (pin "B9") (pinfunction "B9_B9") (pintype "bidirectional"))
      (node (ref "U$13") (pin "1") (pinfunction "TXD_1") (pintype "bidirectional"))
    )
    (net (code "61") (name "RX") (class "Default")
      (node (ref "R15") (pin "2") (pinfunction "2_2") (pintype "passive"))
      (node (ref "U$2") (pin "11") (pinfunction "4Y_11") (pintype "tri_state"))
    )
    (net (code "62") (name "SERVO") (class "Default")
      (node (ref "R5") (pin "1") (pinfunction "1_1") (pintype "passive"))
      (node (ref "R6") (pin "2") (pinfunction "2_2") (pintype "passive"))
      (node (ref "U$2") (pin "12") (pinfunction "4A_12") (pintype "input"))
      (node (ref "U$2") (pin "3") (pinfunction "1Y_3") (pintype "tri_state"))
    )
    (net (code "63") (name "TX") (class "Default")
      (node (ref "IC2") (pin "5") (pinfunction "5_5") (pintype "output"))
      (node (ref "U$2") (pin "1") (pinfunction "1OE_1") (pintype "input"))
    )
    (net (code "64") (name "USART1_RX") (class "Default")
      (node (ref "IC3") (pin "5") (pinfunction "5_5") (pintype "output"))
      (node (ref "U$1") (pin "A10") (pinfunction "A10_A10") (pintype "bidirectional"))
    )
    (net (code "65") (name "USART1_TX") (class "Default")
      (node (ref "R3") (pin "2") (pinfunction "2_2") (pintype "passive"))
      (node (ref "U$1") (pin "A9") (pinfunction "A9_A9") (pintype "bidirectional"))
    )
    (net (code "66") (name "USART3_RX") (class "Default")
      (node (ref "JP10") (pin "3") (pinfunction "3_3") (pintype "passive"))
      (node (ref "U$1") (pin "B11") (pinfunction "B11_B11") (pintype "bidirectional"))
    )
    (net (code "67") (name "USART3_TX") (class "Default")
      (node (ref "JP10") (pin "1") (pinfunction "1_1") (pintype "passive"))
      (node (ref "U$1") (pin "B10") (pinfunction "B10_B10") (pintype "bidirectional"))
    )
    (net (code "68") (name "USBDFU") (class "Default")
      (node (ref "U$1") (pin "A14") (pinfunction "A14_A14") (pintype "bidirectional"))
    )
    (net (code "69") (name "USBDM") (class "Default")
      (node (ref "U$1") (pin "A11") (pinfunction "A11_A11") (pintype "bidirectional"))
    )
    (net (code "70") (name "USBDP") (class "Default")
      (node (ref "U$1") (pin "A12") (pinfunction "A12_A12") (pintype "bidirectional"))
    )
    (net (code "71") (name "VDD") (class "Default")
      (node (ref "C17") (pin "1") (pinfunction "1_1") (pintype "passive"))
      (node (ref "C19") (pin "+") (pinfunction "+_+") (pintype "passive"))
      (node (ref "C3") (pin "1") (pinfunction "1_1") (pintype "passive"))
      (node (ref "C5") (pin "1") (pinfunction "1_1") (pintype "passive"))
      (node (ref "IC1") (pin "VOUT") (pinfunction "VOUT_VOUT") (pintype "output"))
      (node (ref "IC1") (pin "VOUT2") (pinfunction "VOUT_VOUT2") (pintype "output"))
      (node (ref "IC10") (pin "1") (pinfunction "1_1") (pintype "input"))
      (node (ref "IC11") (pin "1") (pinfunction "1_1") (pintype "input"))
      (node (ref "IC3") (pin "6") (pinfunction "VCC_6") (pintype "power_in"))
      (node (ref "IC4") (pin "1") (pinfunction "1_1") (pintype "input"))
      (node (ref "IC5") (pin "1") (pinfunction "1_1") (pintype "input"))
      (node (ref "IC6") (pin "1") (pinfunction "1_1") (pintype "input"))
      (node (ref "IC7") (pin "1") (pinfunction "1_1") (pintype "input"))
      (node (ref "IC8") (pin "1") (pinfunction "1_1") (pintype "input"))
      (node (ref "IC9") (pin "1") (pinfunction "1_1") (pintype "input"))
      (node (ref "R1") (pin "2") (pinfunction "2_2") (pintype "passive"))
      (node (ref "R35") (pin "2") (pinfunction "2_2") (pintype "passive"))
      (node (ref "U$13") (pin "3") (pinfunction "VCC_3") (pintype "power_in"))
    )
    (net (code "72") (name "unconnected-(U$1-Pad3.3V1)") (class "Default")
      (node (ref "U$1") (pin "3.3V1") (pinfunction "3.3V1_3.3V1") (pintype "bidirectional"))
    )
    (net (code "73") (name "unconnected-(U$1-Pad3.3V2)") (class "Default")
      (node (ref "U$1") (pin "3.3V2") (pinfunction "3.3V2_3.3V2") (pintype "bidirectional"))
    )
    (net (code "74") (name "unconnected-(U$1-Pad5V2)") (class "Default")
      (node (ref "U$1") (pin "5V2") (pinfunction "5V2_5V2") (pintype "bidirectional"))
    )
    (net (code "75") (name "unconnected-(U$1-PadA4)") (class "Default")
      (node (ref "U$1") (pin "A4") (pinfunction "A4_A4") (pintype "bidirectional"))
    )
    (net (code "76") (name "unconnected-(U$1-PadA5)") (class "Default")
      (node (ref "U$1") (pin "A5") (pinfunction "A5_A5") (pintype "bidirectional"))
    )
    (net (code "77") (name "unconnected-(U$1-PadA6)") (class "Default")
      (node (ref "U$1") (pin "A6") (pinfunction "A6_A6") (pintype "bidirectional"))
    )
    (net (code "78") (name "unconnected-(U$1-PadA7)") (class "Default")
      (node (ref "U$1") (pin "A7") (pinfunction "A7_A7") (pintype "bidirectional"))
    )
    (net (code "79") (name "unconnected-(U$1-PadA8)") (class "Default")
      (node (ref "U$1") (pin "A8") (pinfunction "A8_A8") (pintype "bidirectional"))
    )
    (net (code "80") (name "unconnected-(U$1-PadA13)") (class "Default")
      (node (ref "U$1") (pin "A13") (pinfunction "A13_A13") (pintype "bidirectional"))
    )
    (net (code "81") (name "unconnected-(U$1-PadA15)") (class "Default")
      (node (ref "U$1") (pin "A15") (pinfunction "A15_A15") (pintype "bidirectional"))
    )
    (net (code "82") (name "unconnected-(U$1-PadB0)") (class "Default")
      (node (ref "U$1") (pin "B0") (pinfunction "B0_B0") (pintype "bidirectional"))
    )
    (net (code "83") (name "unconnected-(U$1-PadB1)") (class "Default")
      (node (ref "U$1") (pin "B1") (pinfunction "B1_B1") (pintype "bidirectional"))
    )
    (net (code "84") (name "unconnected-(U$1-PadB2)") (class "Default")
      (node (ref "U$1") (pin "B2") (pinfunction "B2_B2") (pintype "bidirectional"))
    )
    (net (code "85") (name "unconnected-(U$1-PadB3)") (class "Default")
      (node (ref "U$1") (pin "B3") (pinfunction "B3_B3") (pintype "bidirectional"))
    )
    (net (code "86") (name "unconnected-(U$1-PadB4)") (class "Default")
      (node (ref "U$1") (pin "B4") (pinfunction "B4_B4") (pintype "bidirectional"))
    )
    (net (code "87") (name "unconnected-(U$1-PadB5)") (class "Default")
      (node (ref "U$1") (pin "B5") (pinfunction "B5_B5") (pintype "bidirectional"))
    )
    (net (code "88") (name "unconnected-(U$1-PadB6)") (class "Default")
      (node (ref "U$1") (pin "B6") (pinfunction "B6_B6") (pintype "bidirectional"))
    )
    (net (code "89") (name "unconnected-(U$1-PadB7)") (class "Default")
      (node (ref "U$1") (pin "B7") (pinfunction "B7_B7") (pintype "bidirectional"))
    )
    (net (code "90") (name "unconnected-(U$2-2Y-Pad6)") (class "Default")
      (node (ref "U$2") (pin "6") (pinfunction "2Y_6") (pintype "tri_state"))
    )
    (net (code "91") (name "unconnected-(U$2-3Y-Pad8)") (class "Default")
      (node (ref "U$2") (pin "8") (pinfunction "3Y_8") (pintype "tri_state"))
    )
    (net (code "92") (name "unconnected-(U$13A-VREF-Pad5)") (class "Default")
      (node (ref "U$13") (pin "5") (pinfunction "VREF_5") (pintype "bidirectional"))
    )
  )
)
